# MOSFET_module_V3A.net
KiCad netlist of a schematic drawn in EAGLE
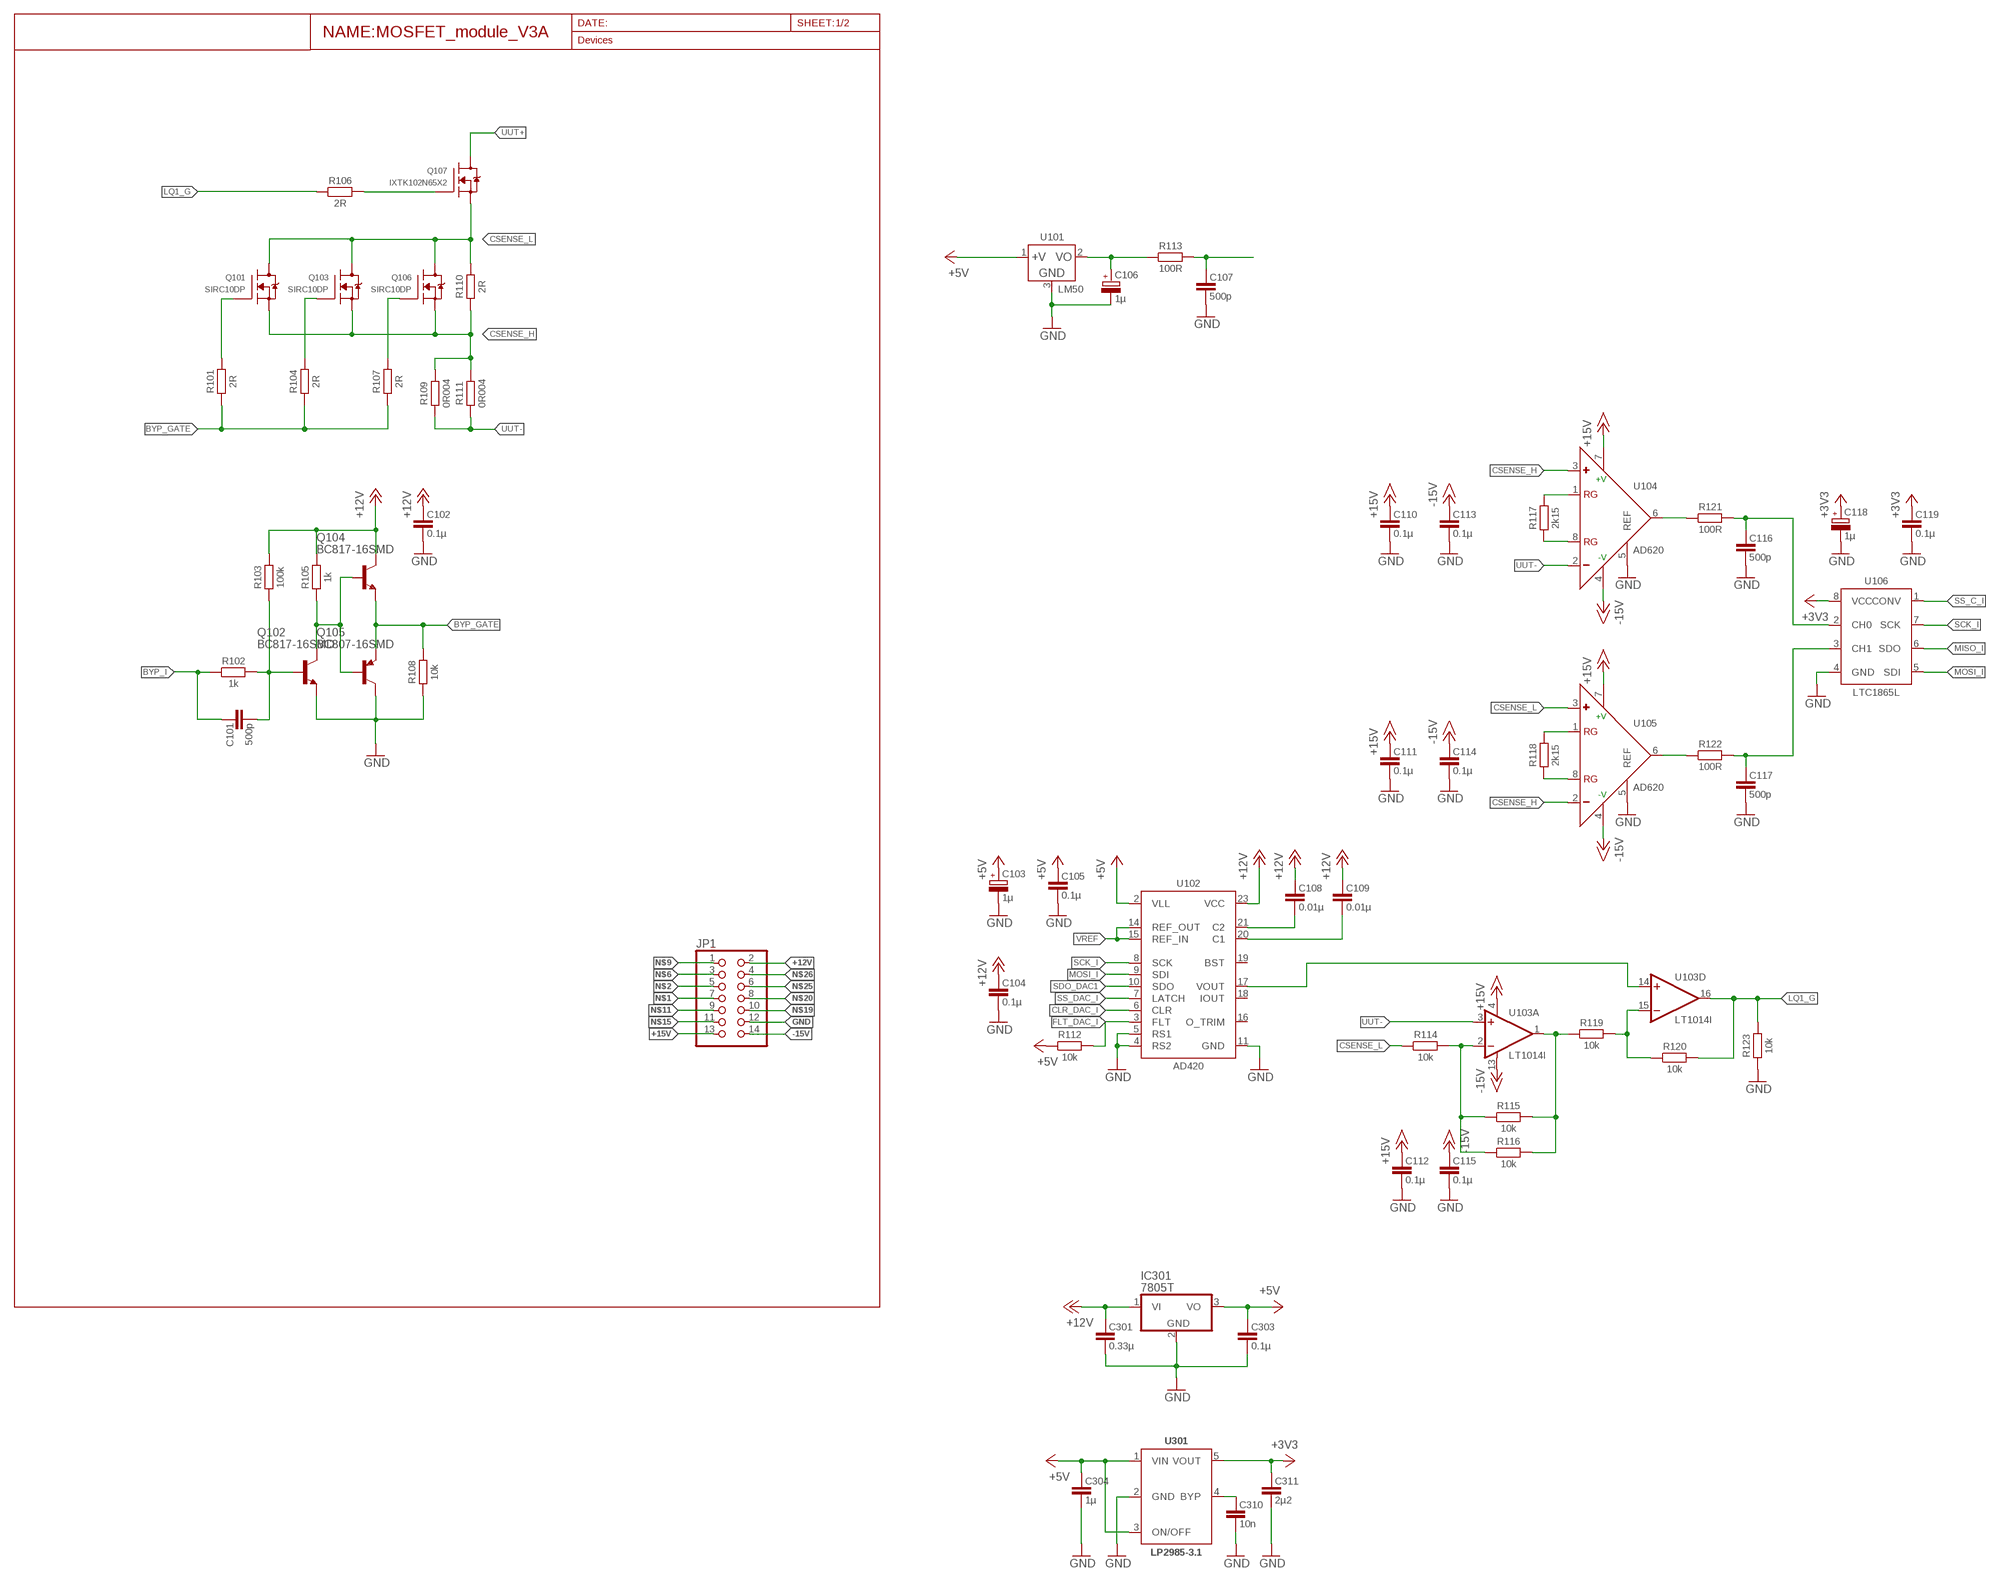
[diagram p0: schematic, sheet 1]
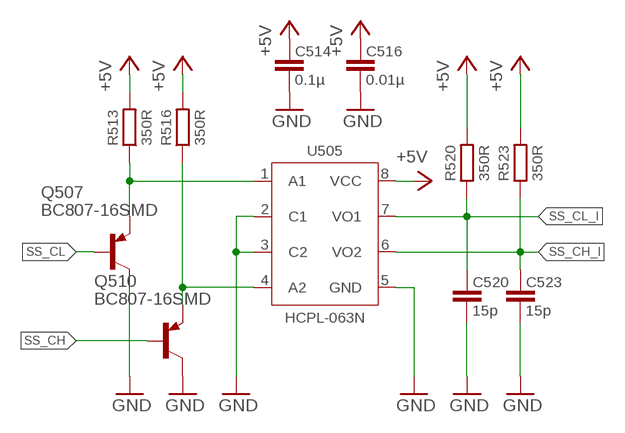
[diagram p1: schematic, sheet 2]

(export (version "E")
  (design (tool "Eeschema 10.0.6"))
  (components
    (comp (ref "C514")
      (value "0.1µ")
      (footprint "eagle-import:C3216")
      (libsource (lib "eagle-import") (part "C-EU-3216"))
    )
    (comp (ref "C516")
      (value "0.01µ")
      (footprint "eagle-import:C3216")
      (libsource (lib "eagle-import") (part "C-EU-3216"))
    )
    (comp (ref "C520")
      (value "15p")
      (footprint "eagle-import:C1608")
      (libsource (lib "eagle-import") (part "C-EU-1608"))
    )
    (comp (ref "C523")
      (value "15p")
      (footprint "eagle-import:C1608")
      (libsource (lib "eagle-import") (part "C-EU-1608"))
    )
    (comp (ref "Q507")
      (value "BC807-16SMD")
      (footprint "eagle-import:SOT23-BEC")
      (libsource (lib "eagle-import") (part "BC807SMD-16"))
    )
    (comp (ref "Q510")
      (value "BC807-16SMD")
      (footprint "eagle-import:SOT23-BEC")
      (libsource (lib "eagle-import") (part "BC807SMD-16"))
    )
    (comp (ref "R513")
      (value "350R")
      (footprint "eagle-import:R1608")
      (libsource (lib "eagle-import") (part "R-EU-1608"))
    )
    (comp (ref "R516")
      (value "350R")
      (footprint "eagle-import:R1608")
      (libsource (lib "eagle-import") (part "R-EU-1608"))
    )
    (comp (ref "R520")
      (value "350R")
      (footprint "eagle-import:R1608")
      (libsource (lib "eagle-import") (part "R-EU-1608"))
    )
    (comp (ref "R523")
      (value "350R")
      (footprint "eagle-import:R1608")
      (libsource (lib "eagle-import") (part "R-EU-1608"))
    )
    (comp (ref "U505")
      (value "HCPL-063N")
      (footprint "eagle-import:SO8")
      (libsource (lib "eagle-import") (part "HCPL-063N"))
    )
    (comp (ref "C101")
      (value "500p")
      (footprint "eagle-import:C1608")
      (libsource (lib "eagle-import") (part "C-EU-1608"))
    )
    (comp (ref "C102")
      (value "0.1µ")
      (footprint "eagle-import:C3216")
      (libsource (lib "eagle-import") (part "C-EU-3216"))
    )
    (comp (ref "C103")
      (value "1µ")
      (footprint "eagle-import:CT3216")
      (libsource (lib "eagle-import") (part "CPOL-3216-A"))
    )
    (comp (ref "C104")
      (value "0.1µ")
      (footprint "eagle-import:C3216")
      (libsource (lib "eagle-import") (part "C-EU-3216"))
    )
    (comp (ref "C105")
      (value "0.1µ")
      (footprint "eagle-import:C3216")
      (libsource (lib "eagle-import") (part "C-EU-3216"))
    )
    (comp (ref "C106")
      (value "1µ")
      (footprint "eagle-import:CT3216")
      (libsource (lib "eagle-import") (part "CPOL-3216-A"))
    )
    (comp (ref "C107")
      (value "500p")
      (footprint "eagle-import:C1608")
      (libsource (lib "eagle-import") (part "C-EU-1608"))
    )
    (comp (ref "C108")
      (value "0.01µ")
      (footprint "eagle-import:C3216")
      (libsource (lib "eagle-import") (part "C-EU-3216"))
    )
    (comp (ref "C109")
      (value "0.01µ")
      (footprint "eagle-import:C3216")
      (libsource (lib "eagle-import") (part "C-EU-3216"))
    )
    (comp (ref "C110")
      (value "0.1µ")
      (footprint "eagle-import:C3216")
      (libsource (lib "eagle-import") (part "C-EU-3216"))
    )
    (comp (ref "C111")
      (value "0.1µ")
      (footprint "eagle-import:C3216")
      (libsource (lib "eagle-import") (part "C-EU-3216"))
    )
    (comp (ref "C112")
      (value "0.1µ")
      (footprint "eagle-import:C3216")
      (libsource (lib "eagle-import") (part "C-EU-3216"))
    )
    (comp (ref "C113")
      (value "0.1µ")
      (footprint "eagle-import:C3216")
      (libsource (lib "eagle-import") (part "C-EU-3216"))
    )
    (comp (ref "C114")
      (value "0.1µ")
      (footprint "eagle-import:C3216")
      (libsource (lib "eagle-import") (part "C-EU-3216"))
    )
    (comp (ref "C115")
      (value "0.1µ")
      (footprint "eagle-import:C3216")
      (libsource (lib "eagle-import") (part "C-EU-3216"))
    )
    (comp (ref "C116")
      (value "500p")
      (footprint "eagle-import:C1608")
      (libsource (lib "eagle-import") (part "C-EU-1608"))
    )
    (comp (ref "C117")
      (value "500p")
      (footprint "eagle-import:C1608")
      (libsource (lib "eagle-import") (part "C-EU-1608"))
    )
    (comp (ref "C118")
      (value "1µ")
      (footprint "eagle-import:CT3216")
      (libsource (lib "eagle-import") (part "CPOL-3216-A"))
    )
    (comp (ref "C119")
      (value "0.1µ")
      (footprint "eagle-import:C3216")
      (libsource (lib "eagle-import") (part "C-EU-3216"))
    )
    (comp (ref "C301")
      (value "0.33µ")
      (footprint "eagle-import:C3216")
      (libsource (lib "eagle-import") (part "C-EU-3216"))
    )
    (comp (ref "C303")
      (value "0.1µ")
      (footprint "eagle-import:C3216")
      (libsource (lib "eagle-import") (part "C-EU-3216"))
    )
    (comp (ref "C304")
      (value "1µ")
      (footprint "eagle-import:C3216")
      (libsource (lib "eagle-import") (part "C-EU-3216"))
    )
    (comp (ref "C310")
      (value "10n")
      (footprint "eagle-import:C3216")
      (libsource (lib "eagle-import") (part "C-EU-3216"))
    )
    (comp (ref "C311")
      (value "2µ2")
      (footprint "eagle-import:C3216")
      (libsource (lib "eagle-import") (part "C-EU-3216"))
    )
    (comp (ref "IC301")
      (value "7805T")
      (footprint "eagle-import:TO220H")
      (libsource (lib "eagle-import") (part "78T05"))
    )
    (comp (ref "JP1")
      (value "PINHD-2X7")
      (footprint "eagle-import:2X07")
      (libsource (lib "eagle-import") (part "PINHD-2X7"))
    )
    (comp (ref "Q101")
      (value "SIRC10DP")
      (footprint "eagle-import:POWERPAK-SO-8")
      (libsource (lib "eagle-import") (part "SIRC10DP"))
    )
    (comp (ref "Q102")
      (value "BC817-16SMD")
      (footprint "eagle-import:SOT23-BEC")
      (libsource (lib "eagle-import") (part "BC817SMD-16"))
    )
    (comp (ref "Q103")
      (value "SIRC10DP")
      (footprint "eagle-import:POWERPAK-SO-8")
      (libsource (lib "eagle-import") (part "SIRC10DP"))
    )
    (comp (ref "Q104")
      (value "BC817-16SMD")
      (footprint "eagle-import:SOT23-BEC")
      (libsource (lib "eagle-import") (part "BC817SMD-16"))
    )
    (comp (ref "Q105")
      (value "BC807-16SMD")
      (footprint "eagle-import:SOT23-BEC")
      (libsource (lib "eagle-import") (part "BC807SMD-16"))
    )
    (comp (ref "Q106")
      (value "SIRC10DP")
      (footprint "eagle-import:POWERPAK-SO-8")
      (libsource (lib "eagle-import") (part "SIRC10DP"))
    )
    (comp (ref "Q107")
      (value "IXTK102N65X2")
      (footprint "eagle-import:TO-264P-V")
      (libsource (lib "eagle-import") (part "IXTK102N65X2-V"))
    )
    (comp (ref "R101")
      (value "2R")
      (footprint "eagle-import:R3216W")
      (libsource (lib "eagle-import") (part "R-EU-3216"))
    )
    (comp (ref "R102")
      (value "1k")
      (footprint "eagle-import:R1608")
      (libsource (lib "eagle-import") (part "R-EU-1608"))
    )
    (comp (ref "R103")
      (value "100k")
      (footprint "eagle-import:R1608")
      (libsource (lib "eagle-import") (part "R-EU-1608"))
    )
    (comp (ref "R104")
      (value "2R")
      (footprint "eagle-import:R3216W")
      (libsource (lib "eagle-import") (part "R-EU-3216"))
    )
    (comp (ref "R105")
      (value "1k")
      (footprint "eagle-import:R1608")
      (libsource (lib "eagle-import") (part "R-EU-1608"))
    )
    (comp (ref "R106")
      (value "2R")
      (footprint "eagle-import:R3216W")
      (libsource (lib "eagle-import") (part "R-EU-3216"))
    )
    (comp (ref "R107")
      (value "2R")
      (footprint "eagle-import:R3216W")
      (libsource (lib "eagle-import") (part "R-EU-3216"))
    )
    (comp (ref "R108")
      (value "10k")
      (footprint "eagle-import:R1608")
      (libsource (lib "eagle-import") (part "R-EU-1608"))
    )
    (comp (ref "R109")
      (value "0R004")
      (footprint "eagle-import:R6332W")
      (libsource (lib "eagle-import") (part "R-EU-6332"))
    )
    (comp (ref "R110")
      (value "2R")
      (footprint "eagle-import:R3216W")
      (libsource (lib "eagle-import") (part "R-EU-3216"))
    )
    (comp (ref "R111")
      (value "0R004")
      (footprint "eagle-import:R6332W")
      (libsource (lib "eagle-import") (part "R-EU-6332"))
    )
    (comp (ref "R112")
      (value "10k")
      (footprint "eagle-import:R1608")
      (libsource (lib "eagle-import") (part "R-EU-1608"))
    )
    (comp (ref "R113")
      (value "100R")
      (footprint "eagle-import:R2012W")
      (libsource (lib "eagle-import") (part "R-EU-2012"))
    )
    (comp (ref "R114")
      (value "10k")
      (footprint "eagle-import:R1608")
      (libsource (lib "eagle-import") (part "R-EU-1608"))
    )
    (comp (ref "R115")
      (value "10k")
      (footprint "eagle-import:R1608")
      (libsource (lib "eagle-import") (part "R-EU-1608"))
    )
    (comp (ref "R116")
      (value "10k")
      (footprint "eagle-import:R1608")
      (libsource (lib "eagle-import") (part "R-EU-1608"))
    )
    (comp (ref "R117")
      (value "2k15")
      (footprint "eagle-import:R2012W")
      (libsource (lib "eagle-import") (part "R-EU-2012"))
    )
    (comp (ref "R118")
      (value "2k15")
      (footprint "eagle-import:R2012W")
      (libsource (lib "eagle-import") (part "R-EU-2012"))
    )
    (comp (ref "R119")
      (value "10k")
      (footprint "eagle-import:R1608")
      (libsource (lib "eagle-import") (part "R-EU-1608"))
    )
    (comp (ref "R120")
      (value "10k")
      (footprint "eagle-import:R1608")
      (libsource (lib "eagle-import") (part "R-EU-1608"))
    )
    (comp (ref "R121")
      (value "100R")
      (footprint "eagle-import:R2012W")
      (libsource (lib "eagle-import") (part "R-EU-2012"))
    )
    (comp (ref "R122")
      (value "100R")
      (footprint "eagle-import:R2012W")
      (libsource (lib "eagle-import") (part "R-EU-2012"))
    )
    (comp (ref "R123")
      (value "10k")
      (footprint "eagle-import:R1608")
      (libsource (lib "eagle-import") (part "R-EU-1608"))
    )
    (comp (ref "U101")
      (value "LM50")
      (footprint "eagle-import:SOT23W")
      (libsource (lib "eagle-import") (part "LM50"))
    )
    (comp (ref "U102")
      (value "AD420")
      (footprint "eagle-import:SO24W")
      (libsource (lib "eagle-import") (part "AD420RW-24"))
    )
    (comp (ref "U103")
      (value "LT1014I")
      (footprint "eagle-import:SO16W")
      (libsource (lib "eagle-import") (part "LT1014ISW"))
    )
    (comp (ref "U104")
      (value "AD620")
      (footprint "eagle-import:SO8")
      (libsource (lib "eagle-import") (part "AD620R-8"))
    )
    (comp (ref "U105")
      (value "AD620")
      (footprint "eagle-import:SO8")
      (libsource (lib "eagle-import") (part "AD620R-8"))
    )
    (comp (ref "U106")
      (value "LTC1865L")
      (footprint "eagle-import:SO8")
      (libsource (lib "eagle-import") (part "LTC1865L"))
    )
    (comp (ref "U301")
      (value "LP2985-3.1")
      (footprint "eagle-import:SOT23-5L")
      (libsource (lib "eagle-import") (part "LP2985-3.1"))
    )
  )
  (nets
    (net (code "1") (name "+3V3") (class "Default")
      (node (ref "C118") (pin "+") (pinfunction "+_+") (pintype "passive"))
      (node (ref "C119") (pin "1") (pinfunction "1_1") (pintype "passive"))
      (node (ref "C311") (pin "1") (pinfunction "1_1") (pintype "passive"))
      (node (ref "U106") (pin "8") (pinfunction "VCC_8") (pintype "power_in"))
      (node (ref "U301") (pin "5") (pinfunction "VOUT_5") (pintype "power_in"))
    )
    (net (code "2") (name "+5V") (class "Default")
      (node (ref "C103") (pin "+") (pinfunction "+_+") (pintype "passive"))
      (node (ref "C105") (pin "1") (pinfunction "1_1") (pintype "passive"))
      (node (ref "C303") (pin "1") (pinfunction "1_1") (pintype "passive"))
      (node (ref "C304") (pin "1") (pinfunction "1_1") (pintype "passive"))
      (node (ref "C514") (pin "1") (pinfunction "1_1") (pintype "passive"))
      (node (ref "C516") (pin "1") (pinfunction "1_1") (pintype "passive"))
      (node (ref "IC301") (pin "3") (pinfunction "VO_3") (pintype "passive"))
      (node (ref "R112") (pin "1") (pinfunction "1_1") (pintype "passive"))
      (node (ref "R513") (pin "2") (pinfunction "2_2") (pintype "passive"))
      (node (ref "R516") (pin "2") (pinfunction "2_2") (pintype "passive"))
      (node (ref "R520") (pin "2") (pinfunction "2_2") (pintype "passive"))
      (node (ref "R523") (pin "2") (pinfunction "2_2") (pintype "passive"))
      (node (ref "U101") (pin "1") (pinfunction "+V_1") (pintype "power_in"))
      (node (ref "U102") (pin "2") (pinfunction "VLL_2") (pintype "bidirectional"))
      (node (ref "U301") (pin "1") (pinfunction "VIN_1") (pintype "power_in"))
      (node (ref "U301") (pin "3") (pinfunction "ON/OFF_3") (pintype "input"))
      (node (ref "U505") (pin "8") (pinfunction "VCC_8") (pintype "power_in"))
    )
    (net (code "3") (name "+12V") (class "Default")
      (node (ref "C102") (pin "1") (pinfunction "1_1") (pintype "passive"))
      (node (ref "C104") (pin "1") (pinfunction "1_1") (pintype "passive"))
      (node (ref "C108") (pin "1") (pinfunction "1_1") (pintype "passive"))
      (node (ref "C109") (pin "1") (pinfunction "1_1") (pintype "passive"))
      (node (ref "C301") (pin "1") (pinfunction "1_1") (pintype "passive"))
      (node (ref "IC301") (pin "1") (pinfunction "VI_1") (pintype "input"))
      (node (ref "JP1") (pin "2") (pinfunction "2_2") (pintype "passive"))
      (node (ref "Q104") (pin "C") (pinfunction "C_C") (pintype "passive"))
      (node (ref "R103") (pin "2") (pinfunction "2_2") (pintype "passive"))
      (node (ref "R105") (pin "2") (pinfunction "2_2") (pintype "passive"))
      (node (ref "U102") (pin "23") (pinfunction "VCC_23") (pintype "bidirectional"))
    )
    (net (code "4") (name "+15V") (class "Default")
      (node (ref "C110") (pin "1") (pinfunction "1_1") (pintype "passive"))
      (node (ref "C111") (pin "1") (pinfunction "1_1") (pintype "passive"))
      (node (ref "C112") (pin "1") (pinfunction "1_1") (pintype "passive"))
      (node (ref "JP1") (pin "13") (pinfunction "13_13") (pintype "passive"))
      (node (ref "U103") (pin "4") (pinfunction "V+_4") (pintype "power_in"))
      (node (ref "U104") (pin "7") (pinfunction "+V_7") (pintype "power_in"))
      (node (ref "U105") (pin "7") (pinfunction "+V_7") (pintype "power_in"))
    )
    (net (code "5") (name "-15V") (class "Default")
      (node (ref "C113") (pin "1") (pinfunction "1_1") (pintype "passive"))
      (node (ref "C114") (pin "1") (pinfunction "1_1") (pintype "passive"))
      (node (ref "C115") (pin "1") (pinfunction "1_1") (pintype "passive"))
      (node (ref "JP1") (pin "14") (pinfunction "14_14") (pintype "passive"))
      (node (ref "U103") (pin "13") (pinfunction "V-_13") (pintype "power_in"))
      (node (ref "U104") (pin "4") (pinfunction "-V_4") (pintype "power_in"))
      (node (ref "U105") (pin "4") (pinfunction "-V_4") (pintype "power_in"))
    )
    (net (code "6") (name "BYP_GATE") (class "Default")
      (node (ref "Q104") (pin "E") (pinfunction "E_E") (pintype "passive"))
      (node (ref "Q105") (pin "E") (pinfunction "E_E") (pintype "passive"))
      (node (ref "R101") (pin "1") (pinfunction "1_1") (pintype "passive"))
      (node (ref "R104") (pin "1") (pinfunction "1_1") (pintype "passive"))
      (node (ref "R107") (pin "1") (pinfunction "1_1") (pintype "passive"))
      (node (ref "R108") (pin "2") (pinfunction "2_2") (pintype "passive"))
    )
    (net (code "7") (name "BYP_I") (class "Default")
      (node (ref "C101") (pin "1") (pinfunction "1_1") (pintype "passive"))
      (node (ref "R102") (pin "1") (pinfunction "1_1") (pintype "passive"))
    )
    (net (code "8") (name "CLR_DAC_I") (class "Default")
      (node (ref "U102") (pin "6") (pinfunction "CLR_6") (pintype "bidirectional"))
    )
    (net (code "9") (name "CSENSE_H") (class "Default")
      (node (ref "Q101") (pin "1") (pinfunction "S_1") (pintype "passive"))
      (node (ref "Q101") (pin "2") (pinfunction "S_2") (pintype "passive"))
      (node (ref "Q101") (pin "3") (pinfunction "S_3") (pintype "passive"))
      (node (ref "Q103") (pin "1") (pinfunction "S_1") (pintype "passive"))
      (node (ref "Q103") (pin "2") (pinfunction "S_2") (pintype "passive"))
      (node (ref "Q103") (pin "3") (pinfunction "S_3") (pintype "passive"))
      (node (ref "Q106") (pin "1") (pinfunction "S_1") (pintype "passive"))
      (node (ref "Q106") (pin "2") (pinfunction "S_2") (pintype "passive"))
      (node (ref "Q106") (pin "3") (pinfunction "S_3") (pintype "passive"))
      (node (ref "R109") (pin "2") (pinfunction "2_2") (pintype "passive"))
      (node (ref "R110") (pin "1") (pinfunction "1_1") (pintype "passive"))
      (node (ref "R111") (pin "2") (pinfunction "2_2") (pintype "passive"))
      (node (ref "U104") (pin "3") (pinfunction "+_3") (pintype "input"))
      (node (ref "U105") (pin "2") (pinfunction "-_2") (pintype "input"))
    )
    (net (code "10") (name "CSENSE_L") (class "Default")
      (node (ref "Q101") (pin "5") (pinfunction "D_5") (pintype "passive"))
      (node (ref "Q103") (pin "5") (pinfunction "D_5") (pintype "passive"))
      (node (ref "Q106") (pin "5") (pinfunction "D_5") (pintype "passive"))
      (node (ref "Q107") (pin "3") (pinfunction "S_3") (pintype "passive"))
      (node (ref "R110") (pin "2") (pinfunction "2_2") (pintype "passive"))
      (node (ref "R114") (pin "1") (pinfunction "1_1") (pintype "passive"))
      (node (ref "U105") (pin "3") (pinfunction "+_3") (pintype "input"))
    )
    (net (code "11") (name "FLT_DAC_I") (class "Default")
      (node (ref "R112") (pin "2") (pinfunction "2_2") (pintype "passive"))
      (node (ref "U102") (pin "3") (pinfunction "FLT_3") (pintype "bidirectional"))
    )
    (net (code "12") (name "GND") (class "Default")
      (node (ref "C102") (pin "2") (pinfunction "2_2") (pintype "passive"))
      (node (ref "C103") (pin "-") (pinfunction "-_-") (pintype "passive"))
      (node (ref "C104") (pin "2") (pinfunction "2_2") (pintype "passive"))
      (node (ref "C105") (pin "2") (pinfunction "2_2") (pintype "passive"))
      (node (ref "C106") (pin "-") (pinfunction "-_-") (pintype "passive"))
      (node (ref "C107") (pin "2") (pinfunction "2_2") (pintype "passive"))
      (node (ref "C110") (pin "2") (pinfunction "2_2") (pintype "passive"))
      (node (ref "C111") (pin "2") (pinfunction "2_2") (pintype "passive"))
      (node (ref "C112") (pin "2") (pinfunction "2_2") (pintype "passive"))
      (node (ref "C113") (pin "2") (pinfunction "2_2") (pintype "passive"))
      (node (ref "C114") (pin "2") (pinfunction "2_2") (pintype "passive"))
      (node (ref "C115") (pin "2") (pinfunction "2_2") (pintype "passive"))
      (node (ref "C116") (pin "2") (pinfunction "2_2") (pintype "passive"))
      (node (ref "C117") (pin "2") (pinfunction "2_2") (pintype "passive"))
      (node (ref "C118") (pin "-") (pinfunction "-_-") (pintype "passive"))
      (node (ref "C119") (pin "2") (pinfunction "2_2") (pintype "passive"))
      (node (ref "C301") (pin "2") (pinfunction "2_2") (pintype "passive"))
      (node (ref "C303") (pin "2") (pinfunction "2_2") (pintype "passive"))
      (node (ref "C304") (pin "2") (pinfunction "2_2") (pintype "passive"))
      (node (ref "C310") (pin "2") (pinfunction "2_2") (pintype "passive"))
      (node (ref "C311") (pin "2") (pinfunction "2_2") (pintype "passive"))
      (node (ref "C514") (pin "2") (pinfunction "2_2") (pintype "passive"))
      (node (ref "C516") (pin "2") (pinfunction "2_2") (pintype "passive"))
      (node (ref "C520") (pin "2") (pinfunction "2_2") (pintype "passive"))
      (node (ref "C523") (pin "2") (pinfunction "2_2") (pintype "passive"))
      (node (ref "IC301") (pin "2") (pinfunction "GND_2") (pintype "passive"))
      (node (ref "JP1") (pin "12") (pinfunction "12_12") (pintype "passive"))
      (node (ref "Q102") (pin "E") (pinfunction "E_E") (pintype "passive"))
      (node (ref "Q105") (pin "C") (pinfunction "C_C") (pintype "passive"))
      (node (ref "Q507") (pin "C") (pinfunction "C_C") (pintype "passive"))
      (node (ref "Q510") (pin "C") (pinfunction "C_C") (pintype "passive"))
      (node (ref "R108") (pin "1") (pinfunction "1_1") (pintype "passive"))
      (node (ref "R123") (pin "1") (pinfunction "1_1") (pintype "passive"))
      (node (ref "U101") (pin "3") (pinfunction "GND_3") (pintype "power_in"))
      (node (ref "U102") (pin "11") (pinfunction "GND_11") (pintype "bidirectional"))
      (node (ref "U102") (pin "4") (pinfunction "RS2_4") (pintype "bidirectional"))
      (node (ref "U102") (pin "5") (pinfunction "RS1_5") (pintype "bidirectional"))
      (node (ref "U104") (pin "5") (pinfunction "REF_5") (pintype "passive"))
      (node (ref "U105") (pin "5") (pinfunction "REF_5") (pintype "passive"))
      (node (ref "U106") (pin "4") (pinfunction "GND_4") (pintype "bidirectional"))
      (node (ref "U301") (pin "2") (pinfunction "GND_2") (pintype "power_in"))
      (node (ref "U505") (pin "2") (pinfunction "C1_2") (pintype "input"))
      (node (ref "U505") (pin "3") (pinfunction "C2_3") (pintype "input"))
      (node (ref "U505") (pin "5") (pinfunction "GND_5") (pintype "power_in"))
    )
    (net (code "13") (name "LQ1_G") (class "Default")
      (node (ref "R106") (pin "1") (pinfunction "1_1") (pintype "passive"))
      (node (ref "R120") (pin "2") (pinfunction "2_2") (pintype "passive"))
      (node (ref "R123") (pin "2") (pinfunction "2_2") (pintype "passive"))
      (node (ref "U103") (pin "16") (pinfunction "OUT_16") (pintype "output"))
    )
    (net (code "14") (name "MISO_I") (class "Default")
      (node (ref "U106") (pin "6") (pinfunction "SDO_6") (pintype "output"))
    )
    (net (code "15") (name "MOSI_I") (class "Default")
      (node (ref "U102") (pin "9") (pinfunction "SDI_9") (pintype "bidirectional"))
      (node (ref "U106") (pin "5") (pinfunction "SDI_5") (pintype "input"))
    )
    (net (code "16") (name "N$1") (class "Default")
      (node (ref "JP1") (pin "7") (pinfunction "7_7") (pintype "passive"))
    )
    (net (code "17") (name "N$2") (class "Default")
      (node (ref "JP1") (pin "5") (pinfunction "5_5") (pintype "passive"))
    )
    (net (code "18") (name "N$6") (class "Default")
      (node (ref "JP1") (pin "3") (pinfunction "3_3") (pintype "passive"))
    )
    (net (code "19") (name "N$9") (class "Default")
      (node (ref "JP1") (pin "1") (pinfunction "1_1") (pintype "passive"))
    )
    (net (code "20") (name "N$11") (class "Default")
      (node (ref "JP1") (pin "9") (pinfunction "9_9") (pintype "passive"))
    )
    (net (code "21") (name "N$15") (class "Default")
      (node (ref "JP1") (pin "11") (pinfunction "11_11") (pintype "passive"))
    )
    (net (code "22") (name "N$19") (class "Default")
      (node (ref "JP1") (pin "10") (pinfunction "10_10") (pintype "passive"))
    )
    (net (code "23") (name "N$20") (class "Default")
      (node (ref "JP1") (pin "8") (pinfunction "8_8") (pintype "passive"))
    )
    (net (code "24") (name "N$25") (class "Default")
      (node (ref "JP1") (pin "6") (pinfunction "6_6") (pintype "passive"))
    )
    (net (code "25") (name "N$26") (class "Default")
      (node (ref "JP1") (pin "4") (pinfunction "4_4") (pintype "passive"))
    )
    (net (code "26") (name "Net-(C101-Pad2)") (class "Default")
      (node (ref "C101") (pin "2") (pinfunction "2_2") (pintype "passive"))
      (node (ref "Q102") (pin "B") (pinfunction "B_B") (pintype "passive"))
      (node (ref "R102") (pin "2") (pinfunction "2_2") (pintype "passive"))
      (node (ref "R103") (pin "1") (pinfunction "1_1") (pintype "passive"))
    )
    (net (code "27") (name "Net-(C107-Pad1)") (class "Default")
      (node (ref "C107") (pin "1") (pinfunction "1_1") (pintype "passive"))
      (node (ref "R113") (pin "2") (pinfunction "2_2") (pintype "passive"))
    )
    (net (code "28") (name "Net-(Q101-G)") (class "Default")
      (node (ref "Q101") (pin "4") (pinfunction "G_4") (pintype "passive"))
      (node (ref "R101") (pin "2") (pinfunction "2_2") (pintype "passive"))
    )
    (net (code "29") (name "Net-(Q102-PadC)") (class "Default")
      (node (ref "Q102") (pin "C") (pinfunction "C_C") (pintype "passive"))
      (node (ref "Q104") (pin "B") (pinfunction "B_B") (pintype "passive"))
      (node (ref "Q105") (pin "B") (pinfunction "B_B") (pintype "passive"))
      (node (ref "R105") (pin "1") (pinfunction "1_1") (pintype "passive"))
    )
    (net (code "30") (name "Net-(Q103-G)") (class "Default")
      (node (ref "Q103") (pin "4") (pinfunction "G_4") (pintype "passive"))
      (node (ref "R104") (pin "2") (pinfunction "2_2") (pintype "passive"))
    )
    (net (code "31") (name "Net-(Q106-G)") (class "Default")
      (node (ref "Q106") (pin "4") (pinfunction "G_4") (pintype "passive"))
      (node (ref "R107") (pin "2") (pinfunction "2_2") (pintype "passive"))
    )
    (net (code "32") (name "Net-(Q107-G)") (class "Default")
      (node (ref "Q107") (pin "1") (pinfunction "G_1") (pintype "passive"))
      (node (ref "R106") (pin "2") (pinfunction "2_2") (pintype "passive"))
    )
    (net (code "33") (name "Net-(R117-Pad1)") (class "Default")
      (node (ref "R117") (pin "1") (pinfunction "1_1") (pintype "passive"))
      (node (ref "U104") (pin "8") (pinfunction "RG_8") (pintype "passive"))
    )
    (net (code "34") (name "Net-(R117-Pad2)") (class "Default")
      (node (ref "R117") (pin "2") (pinfunction "2_2") (pintype "passive"))
      (node (ref "U104") (pin "1") (pinfunction "RG_1") (pintype "passive"))
    )
    (net (code "35") (name "Net-(R118-Pad1)") (class "Default")
      (node (ref "R118") (pin "1") (pinfunction "1_1") (pintype "passive"))
      (node (ref "U105") (pin "8") (pinfunction "RG_8") (pintype "passive"))
    )
    (net (code "36") (name "Net-(R118-Pad2)") (class "Default")
      (node (ref "R118") (pin "2") (pinfunction "2_2") (pintype "passive"))
      (node (ref "U105") (pin "1") (pinfunction "RG_1") (pintype "passive"))
    )
    (net (code "37") (name "Net-(U101-VO)") (class "Default")
      (node (ref "C106") (pin "+") (pinfunction "+_+") (pintype "passive"))
      (node (ref "R113") (pin "1") (pinfunction "1_1") (pintype "passive"))
      (node (ref "U101") (pin "2") (pinfunction "VO_2") (pintype "output"))
    )
    (net (code "38") (name "Net-(U102-C1)") (class "Default")
      (node (ref "C109") (pin "2") (pinfunction "2_2") (pintype "passive"))
      (node (ref "U102") (pin "20") (pinfunction "C1_20") (pintype "bidirectional"))
    )
    (net (code "39") (name "Net-(U102-C2)") (class "Default")
      (node (ref "C108") (pin "2") (pinfunction "2_2") (pintype "passive"))
      (node (ref "U102") (pin "21") (pinfunction "C2_21") (pintype "bidirectional"))
    )
    (net (code "40") (name "Net-(U102-VOUT)") (class "Default")
      (node (ref "U102") (pin "17") (pinfunction "VOUT_17") (pintype "bidirectional"))
      (node (ref "U103") (pin "14") (pinfunction "+IN_14") (pintype "input"))
    )
    (net (code "41") (name "Net-(U103A--IN)") (class "Default")
      (node (ref "R114") (pin "2") (pinfunction "2_2") (pintype "passive"))
      (node (ref "R115") (pin "1") (pinfunction "1_1") (pintype "passive"))
      (node (ref "R116") (pin "1") (pinfunction "1_1") (pintype "passive"))
      (node (ref "U103") (pin "2") (pinfunction "-IN_2") (pintype "input"))
    )
    (net (code "42") (name "Net-(U103A-OUT)") (class "Default")
      (node (ref "R115") (pin "2") (pinfunction "2_2") (pintype "passive"))
      (node (ref "R116") (pin "2") (pinfunction "2_2") (pintype "passive"))
      (node (ref "R119") (pin "1") (pinfunction "1_1") (pintype "passive"))
      (node (ref "U103") (pin "1") (pinfunction "OUT_1") (pintype "output"))
    )
    (net (code "43") (name "Net-(U103D--IN)") (class "Default")
      (node (ref "R119") (pin "2") (pinfunction "2_2") (pintype "passive"))
      (node (ref "R120") (pin "1") (pinfunction "1_1") (pintype "passive"))
      (node (ref "U103") (pin "15") (pinfunction "-IN_15") (pintype "input"))
    )
    (net (code "44") (name "Net-(U104-OUT)") (class "Default")
      (node (ref "R121") (pin "1") (pinfunction "1_1") (pintype "passive"))
      (node (ref "U104") (pin "6") (pinfunction "OUT_6") (pintype "output"))
    )
    (net (code "45") (name "Net-(U105-OUT)") (class "Default")
      (node (ref "R122") (pin "1") (pinfunction "1_1") (pintype "passive"))
      (node (ref "U105") (pin "6") (pinfunction "OUT_6") (pintype "output"))
    )
    (net (code "46") (name "Net-(U106-CH0)") (class "Default")
      (node (ref "C116") (pin "1") (pinfunction "1_1") (pintype "passive"))
      (node (ref "R121") (pin "2") (pinfunction "2_2") (pintype "passive"))
      (node (ref "U106") (pin "2") (pinfunction "CH0_2") (pintype "input"))
    )
    (net (code "47") (name "Net-(U106-CH1)") (class "Default")
      (node (ref "C117") (pin "1") (pinfunction "1_1") (pintype "passive"))
      (node (ref "R122") (pin "2") (pinfunction "2_2") (pintype "passive"))
      (node (ref "U106") (pin "3") (pinfunction "CH1_3") (pintype "input"))
    )
    (net (code "48") (name "Net-(U301-BYP)") (class "Default")
      (node (ref "C310") (pin "1") (pinfunction "1_1") (pintype "passive"))
      (node (ref "U301") (pin "4") (pinfunction "BYP_4") (pintype "power_in"))
    )
    (net (code "49") (name "Net-(U505-A1)") (class "Default")
      (node (ref "Q507") (pin "E") (pinfunction "E_E") (pintype "passive"))
      (node (ref "R513") (pin "1") (pinfunction "1_1") (pintype "passive"))
      (node (ref "U505") (pin "1") (pinfunction "A1_1") (pintype "input"))
    )
    (net (code "50") (name "Net-(U505-A2)") (class "Default")
      (node (ref "Q510") (pin "E") (pinfunction "E_E") (pintype "passive"))
      (node (ref "R516") (pin "1") (pinfunction "1_1") (pintype "passive"))
      (node (ref "U505") (pin "4") (pinfunction "A2_4") (pintype "input"))
    )
    (net (code "51") (name "SCK_I") (class "Default")
      (node (ref "U102") (pin "8") (pinfunction "SCK_8") (pintype "bidirectional"))
      (node (ref "U106") (pin "7") (pinfunction "SCK_7") (pintype "input"))
    )
    (net (code "52") (name "SDO_DAC1") (class "Default")
      (node (ref "U102") (pin "10") (pinfunction "SDO_10") (pintype "bidirectional"))
    )
    (net (code "53") (name "SS_CH") (class "Default")
      (node (ref "Q510") (pin "B") (pinfunction "B_B") (pintype "passive"))
    )
    (net (code "54") (name "SS_CH_I") (class "Default")
      (node (ref "C523") (pin "1") (pinfunction "1_1") (pintype "passive"))
      (node (ref "R523") (pin "1") (pinfunction "1_1") (pintype "passive"))
      (node (ref "U505") (pin "6") (pinfunction "VO2_6") (pintype "output"))
    )
    (net (code "55") (name "SS_CL") (class "Default")
      (node (ref "Q507") (pin "B") (pinfunction "B_B") (pintype "passive"))
    )
    (net (code "56") (name "SS_CL_I") (class "Default")
      (node (ref "C520") (pin "1") (pinfunction "1_1") (pintype "passive"))
      (node (ref "R520") (pin "1") (pinfunction "1_1") (pintype "passive"))
      (node (ref "U505") (pin "7") (pinfunction "VO1_7") (pintype "output"))
    )
    (net (code "57") (name "SS_C_I") (class "Default")
      (node (ref "U106") (pin "1") (pinfunction "CONV_1") (pintype "input"))
    )
    (net (code "58") (name "SS_DAC_I") (class "Default")
      (node (ref "U102") (pin "7") (pinfunction "LATCH_7") (pintype "bidirectional"))
    )
    (net (code "59") (name "UUT+") (class "Default")
      (node (ref "Q107") (pin "2") (pinfunction "D_2") (pintype "passive"))
    )
    (net (code "60") (name "UUT-") (class "Default")
      (node (ref "R109") (pin "1") (pinfunction "1_1") (pintype "passive"))
      (node (ref "R111") (pin "1") (pinfunction "1_1") (pintype "passive"))
      (node (ref "U103") (pin "3") (pinfunction "+IN_3") (pintype "input"))
      (node (ref "U104") (pin "2") (pinfunction "-_2") (pintype "input"))
    )
    (net (code "61") (name "VREF") (class "Default")
      (node (ref "U102") (pin "14") (pinfunction "REF_OUT_14") (pintype "bidirectional"))
      (node (ref "U102") (pin "15") (pinfunction "REF_IN_15") (pintype "bidirectional"))
    )
    (net (code "62") (name "unconnected-(U102-BST-Pad19)") (class "Default")
      (node (ref "U102") (pin "19") (pinfunction "BST_19") (pintype "bidirectional"))
    )
    (net (code "63") (name "unconnected-(U102-IOUT-Pad18)") (class "Default")
      (node (ref "U102") (pin "18") (pinfunction "IOUT_18") (pintype "bidirectional"))
    )
    (net (code "64") (name "unconnected-(U102-O_TRIM-Pad16)") (class "Default")
      (node (ref "U102") (pin "16") (pinfunction "O_TRIM_16") (pintype "bidirectional"))
    )
  )
)
